# TemperatureSensor.net
KiCad netlist of a schematic drawn in Altium Designer
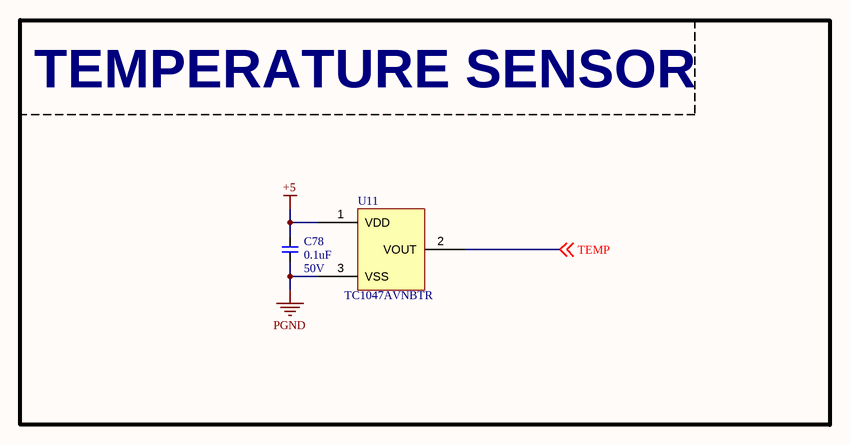
[diagram p0: TemperatureSensor.SchDoc]

(export (version "E")
  (design (tool "Eeschema 10.0.6"))
  (components
    (comp (ref "C78")
      (value "0.1uF")
      (footprint "CAP_C_1608X80")
      (description "CAP")
      (fields (field (name "VOLTAGE") "50V"))
      (libsource (lib "LABLIB") (part "_CAP_C_2"))
    )
    (comp (ref "U11")
      (value "TC1047AVNBTR")
      (footprint "SOT-23")
      (libsource (lib "KIENASIY123_LIB") (part "TC1047AVNBTR"))
    )
  )
  (nets
    (net (code "1") (name "+5") (class "Default")
      (node (ref "C78") (pin "1") (pinfunction "1_1") (pintype "passive"))
      (node (ref "U11") (pin "1") (pinfunction "VDD_1") (pintype "passive"))
    )
    (net (code "2") (name "PGND") (class "Default")
      (node (ref "C78") (pin "2") (pinfunction "2_2") (pintype "passive"))
      (node (ref "U11") (pin "3") (pinfunction "VSS_3") (pintype "passive"))
    )
    (net (code "3") (name "TEMP") (class "Default")
      (node (ref "U11") (pin "2") (pinfunction "VOUT_2") (pintype "passive"))
    )
  )
)
